# MC33797.net
KiCad netlist of a schematic drawn in Altium Designer
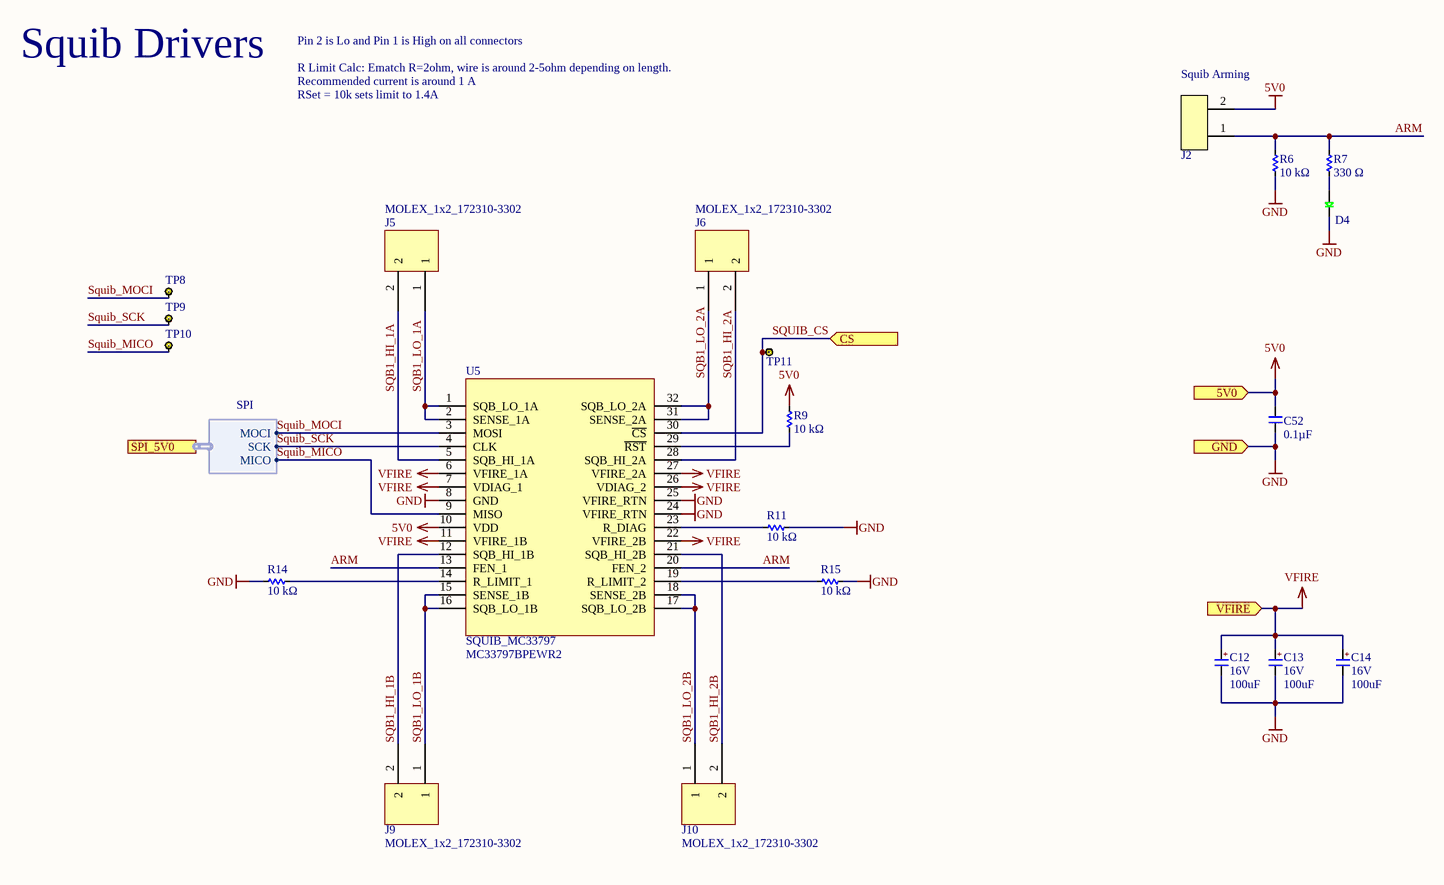
[diagram p0: MC33797.SchDoc]

(export (version "E")
  (design (tool "Eeschema 10.0.6"))
  (components
    (comp (ref "C12")
      (value "TPSC107M016R0200")
      (footprint "CAPCP6032X28N")
      (description "Cap Tant Solid 100uF 16V C CASE 20% (6 X 3.2 X 2.6mm) SMD 6032-28 0.2 Ohm 125°C T/R")
      (fields
        (field (name "CAPACITANCE") "100uF")
        (field (name "VOLTAGE RATING") "16V")
        (field (name "TOLERANCE") "20%")
      )
      (libsource (lib "Stanford Student Space Initiative") (part "CAP_TANT"))
    )
    (comp (ref "C13")
      (value "TPSC107M016R0200")
      (footprint "CAPCP6032X28N")
      (description "Cap Tant Solid 100uF 16V C CASE 20% (6 X 3.2 X 2.6mm) SMD 6032-28 0.2 Ohm 125°C T/R")
      (fields
        (field (name "CAPACITANCE") "100uF")
        (field (name "VOLTAGE RATING") "16V")
        (field (name "TOLERANCE") "20%")
      )
      (libsource (lib "Stanford Student Space Initiative") (part "CAP_TANT"))
    )
    (comp (ref "C14")
      (value "TPSC107M016R0200")
      (footprint "CAPCP6032X28N")
      (description "Cap Tant Solid 100uF 16V C CASE 20% (6 X 3.2 X 2.6mm) SMD 6032-28 0.2 Ohm 125°C T/R")
      (fields
        (field (name "CAPACITANCE") "100uF")
        (field (name "VOLTAGE RATING") "16V")
        (field (name "TOLERANCE") "20%")
      )
      (libsource (lib "Stanford Student Space Initiative") (part "CAP_TANT"))
    )
    (comp (ref "C52")
      (value "490-1519-1-ND")
      (footprint "C0603")
      (description "CAP CER 0603 0.1µF X7R 50V 10%")
      (fields
        (field (name "CAPACITANCE (SHORTHAND)") "0.1µF")
        (field (name "MANUFACTURER") "Murata Electronics North America")
      )
      (libsource (lib "Stanford Student Space Initiative") (part "__template_cap"))
    )
    (comp (ref "D4")
      (value "LED_C503B-GCS-CB0C0781")
      (footprint "LED_TH_5MM")
      (description "LED GREEN CLEAR 5MM ROUND T/H")
      (fields
        (field (name "MANUFACTURER") "Cree")
        (field (name "MANUFACTURER PART NUMBER") "C503B-GCS-CB0C0781")
      )
      (libsource (lib "Stanford Student Space Initiative") (part "LED_C503B-GCS-CB0C0781"))
    )
    (comp (ref "J2")
      (value "CONN_1x2")
      (footprint "CONN_1x2_100MIL")
      (description "CONN HEADER 2POS VERT T/H")
      (fields (field (name "MANUFACTURER PART NUMBER") "77311-118-02LF") (field (name "MANUFACTURER") "FCI"))
      (libsource (lib "Stanford Student Space Initiative") (part "Symbol"))
    )
    (comp (ref "J5")
      (value "MOLEX_1x2_172310-3302")
      (footprint "Molex 172310-xx02")
      (description "ULTRAFIT CONN HEADER R/A 2POS 3.5MM")
      (libsource (lib "") (part "MOLEX_1x2_1723101102_3"))
    )
    (comp (ref "J6")
      (value "MOLEX_1x2_172310-3302")
      (footprint "Molex 172310-xx02")
      (description "ULTRAFIT CONN HEADER R/A 2POS 3.5MM")
      (libsource (lib "Stanford Student Space Initiative") (part "MOLEX_1x2_1723101102"))
    )
    (comp (ref "J9")
      (value "MOLEX_1x2_172310-3302")
      (footprint "Molex 172310-xx02")
      (description "ULTRAFIT CONN HEADER R/A 2POS 3.5MM")
      (libsource (lib "") (part "MOLEX_1x2_1723101102_2"))
    )
    (comp (ref "J10")
      (value "MOLEX_1x2_172310-3302")
      (footprint "Molex 172310-xx02")
      (description "ULTRAFIT CONN HEADER R/A 2POS 3.5MM")
      (libsource (lib "") (part "MOLEX_1x2_1723101102_1"))
    )
    (comp (ref "R6")
      (value "311-10.0KHRCT-ND")
      (footprint "R0603")
      (description "RES SMD 10K OHM 1% 1/10W 0603")
      (fields
        (field (name "RESISTANCE") "10 kΩ")
        (field (name "MANUFACTURER PART NUMBER") "RC0603FR-0710KL")
        (field (name "MANUFACTURER") "Yageo")
      )
      (libsource (lib "Stanford Student Space Initiative") (part "__template_resistor"))
    )
    (comp (ref "R7")
      (value "311-330HRCT-ND")
      (footprint "R0603")
      (description "RES SMD 330 OHM 1% 1/10W 0603")
      (fields
        (field (name "RESISTANCE") "330 Ω")
        (field (name "MANUFACTURER PART NUMBER") "RC0603FR-07330RL")
        (field (name "MANUFACTURER") "Yageo")
      )
      (libsource (lib "Stanford Student Space Initiative") (part "__template_resistor"))
    )
    (comp (ref "R9")
      (value "311-10.0KHRCT-ND")
      (footprint "R0603")
      (description "RES SMD 10K OHM 1% 1/10W 0603")
      (fields
        (field (name "RESISTANCE") "10 kΩ")
        (field (name "MANUFACTURER PART NUMBER") "RC0603FR-0710KL")
        (field (name "MANUFACTURER") "Yageo")
      )
      (libsource (lib "Stanford Student Space Initiative") (part "__template_resistor"))
    )
    (comp (ref "R11")
      (value "311-10.0KHRCT-ND")
      (footprint "R0603")
      (description "RES SMD 10K OHM 1% 1/10W 0603")
      (fields
        (field (name "RESISTANCE") "10 kΩ")
        (field (name "MANUFACTURER PART NUMBER") "RC0603FR-0710KL")
        (field (name "MANUFACTURER") "Yageo")
      )
      (libsource (lib "Stanford Student Space Initiative") (part "__template_resistor"))
    )
    (comp (ref "R14")
      (value "311-10.0KHRCT-ND")
      (footprint "R0603")
      (description "RES SMD 10K OHM 1% 1/10W 0603")
      (fields
        (field (name "RESISTANCE") "10 kΩ")
        (field (name "MANUFACTURER PART NUMBER") "RC0603FR-0710KL")
        (field (name "MANUFACTURER") "Yageo")
      )
      (libsource (lib "Stanford Student Space Initiative") (part "__template_resistor"))
    )
    (comp (ref "R15")
      (value "311-10.0KHRCT-ND")
      (footprint "R0603")
      (description "RES SMD 10K OHM 1% 1/10W 0603")
      (fields
        (field (name "RESISTANCE") "10 kΩ")
        (field (name "MANUFACTURER PART NUMBER") "RC0603FR-0710KL")
        (field (name "MANUFACTURER") "Yageo")
      )
      (libsource (lib "Stanford Student Space Initiative") (part "__template_resistor"))
    )
    (comp (ref "TP8")
      (value "TEST_POINT_BLACK_KEYSTONE_5001")
      (footprint "TEST_POINT_BLACK_KEYSTONE_5001-Footprint-1")
      (description "BLACK T/H TEST POINT")
      (fields
        (field (name "MANUFACTURER PART NUMBER") "5001")
        (field (name "MANUFACTURER") "Keystone Electronics")
      )
      (libsource (lib "Stanford Student Space Initiative") (part "TEST_POINT_BLACK_KEYSTONE_5001"))
    )
    (comp (ref "TP9")
      (value "TEST_POINT_BLACK_KEYSTONE_5001")
      (footprint "TEST_POINT_BLACK_KEYSTONE_5001-Footprint-1")
      (description "BLACK T/H TEST POINT")
      (fields
        (field (name "MANUFACTURER PART NUMBER") "5001")
        (field (name "MANUFACTURER") "Keystone Electronics")
      )
      (libsource (lib "Stanford Student Space Initiative") (part "TEST_POINT_BLACK_KEYSTONE_5001"))
    )
    (comp (ref "TP10")
      (value "TEST_POINT_BLACK_KEYSTONE_5001")
      (footprint "TEST_POINT_BLACK_KEYSTONE_5001-Footprint-1")
      (description "BLACK T/H TEST POINT")
      (fields
        (field (name "MANUFACTURER PART NUMBER") "5001")
        (field (name "MANUFACTURER") "Keystone Electronics")
      )
      (libsource (lib "Stanford Student Space Initiative") (part "TEST_POINT_BLACK_KEYSTONE_5001"))
    )
    (comp (ref "TP11")
      (value "TEST_POINT_BLACK_KEYSTONE_5001")
      (footprint "TEST_POINT_BLACK_KEYSTONE_5001-Footprint-1")
      (description "BLACK T/H TEST POINT")
      (fields
        (field (name "MANUFACTURER PART NUMBER") "5001")
        (field (name "MANUFACTURER") "Keystone Electronics")
      )
      (libsource (lib "Stanford Student Space Initiative") (part "TEST_POINT_BLACK_KEYSTONE_5001"))
    )
    (comp (ref "U5")
      (value "SQUIB_MC33797")
      (footprint "SOT1762-1")
      (fields
        (field (name "MANUFACTURER") "NXP USA Inc.")
        (field (name "MANUFACTURER PART NUMBER") "MC33797BPEWR2")
      )
      (libsource (lib "Stanford Student Space Initiative") (part "SQUIB_MC33797"))
    )
  )
  (nets
    (net (code "2") (name "/ARM") (class "Default")
      (node (ref "J2") (pin "1") (pinfunction "1_1") (pintype "passive"))
      (node (ref "R6") (pin "1") (pinfunction "1_1") (pintype "passive"))
      (node (ref "R7") (pin "2") (pinfunction "2_2") (pintype "passive"))
      (node (ref "U5") (pin "13") (pinfunction "FEN_1_13") (pintype "passive"))
      (node (ref "U5") (pin "20") (pinfunction "FEN_2_20") (pintype "passive"))
    )
    (net (code "3") (name "/SQB1_HI_1A") (class "Default")
      (node (ref "J5") (pin "2") (pinfunction "2_2") (pintype "passive"))
      (node (ref "U5") (pin "5") (pinfunction "SQB_HI_1A_5") (pintype "passive"))
    )
    (net (code "4") (name "/SQB1_HI_1B") (class "Default")
      (node (ref "J9") (pin "2") (pinfunction "2_2") (pintype "passive"))
      (node (ref "U5") (pin "12") (pinfunction "SQB_HI_1B_12") (pintype "passive"))
    )
    (net (code "5") (name "/SQB1_HI_2A") (class "Default")
      (node (ref "J6") (pin "2") (pinfunction "2_2") (pintype "passive"))
      (node (ref "U5") (pin "28") (pinfunction "SQB_HI_2A_28") (pintype "passive"))
    )
    (net (code "6") (name "/SQB1_HI_2B") (class "Default")
      (node (ref "J10") (pin "2") (pinfunction "2_2") (pintype "passive"))
      (node (ref "U5") (pin "21") (pinfunction "SQB_HI_2B_21") (pintype "passive"))
    )
    (net (code "7") (name "/SQB1_LO_1A") (class "Default")
      (node (ref "J5") (pin "1") (pinfunction "1_1") (pintype "passive"))
      (node (ref "U5") (pin "1") (pinfunction "SQB_LO_1A_1") (pintype "passive"))
      (node (ref "U5") (pin "2") (pinfunction "SENSE_1A_2") (pintype "passive"))
    )
    (net (code "8") (name "/SQB1_LO_1B") (class "Default")
      (node (ref "J9") (pin "1") (pinfunction "1_1") (pintype "passive"))
      (node (ref "U5") (pin "15") (pinfunction "SENSE_1B_15") (pintype "passive"))
      (node (ref "U5") (pin "16") (pinfunction "SQB_LO_1B_16") (pintype "passive"))
    )
    (net (code "9") (name "/SQB1_LO_2A") (class "Default")
      (node (ref "J6") (pin "1") (pinfunction "1_1") (pintype "passive"))
      (node (ref "U5") (pin "31") (pinfunction "SENSE_2A_31") (pintype "passive"))
      (node (ref "U5") (pin "32") (pinfunction "SQB_LO_2A_32") (pintype "passive"))
    )
    (net (code "10") (name "/SQB1_LO_2B") (class "Default")
      (node (ref "J10") (pin "1") (pinfunction "1_1") (pintype "passive"))
      (node (ref "U5") (pin "17") (pinfunction "SQB_LO_2B_17") (pintype "passive"))
      (node (ref "U5") (pin "18") (pinfunction "SENSE_2B_18") (pintype "passive"))
    )
    (net (code "11") (name "/SQUIB_CS") (class "Default")
      (node (ref "TP11") (pin "1") (pinfunction "1_1") (pintype "passive"))
      (node (ref "U5") (pin "30") (pinfunction "~{CS}_30") (pintype "passive"))
    )
    (net (code "12") (name "/Squib_MICO") (class "Default")
      (node (ref "TP10") (pin "1") (pinfunction "1_1") (pintype "passive"))
      (node (ref "U5") (pin "9") (pinfunction "MISO_9") (pintype "passive"))
    )
    (net (code "13") (name "/Squib_MOCI") (class "Default")
      (node (ref "TP8") (pin "1") (pinfunction "1_1") (pintype "passive"))
      (node (ref "U5") (pin "3") (pinfunction "MOSI_3") (pintype "passive"))
    )
    (net (code "14") (name "/Squib_SCK") (class "Default")
      (node (ref "TP9") (pin "1") (pinfunction "1_1") (pintype "passive"))
      (node (ref "U5") (pin "4") (pinfunction "CLK_4") (pintype "passive"))
    )
    (net (code "16") (name "5V0") (class "Default")
      (node (ref "C52") (pin "1") (pintype "passive"))
      (node (ref "J2") (pin "2") (pinfunction "2_2") (pintype "passive"))
      (node (ref "R9") (pin "2") (pinfunction "2_2") (pintype "passive"))
      (node (ref "U5") (pin "10") (pinfunction "VDD_10") (pintype "passive"))
    )
    (net (code "17") (name "GND") (class "Default")
      (node (ref "C12") (pin "2") (pinfunction "K_2") (pintype "passive"))
      (node (ref "C13") (pin "2") (pinfunction "K_2") (pintype "passive"))
      (node (ref "C14") (pin "2") (pinfunction "K_2") (pintype "passive"))
      (node (ref "C52") (pin "2") (pintype "passive"))
      (node (ref "D4") (pin "2") (pinfunction "K_2") (pintype "passive"))
      (node (ref "R11") (pin "2") (pinfunction "2_2") (pintype "passive"))
      (node (ref "R14") (pin "1") (pinfunction "1_1") (pintype "passive"))
      (node (ref "R15") (pin "2") (pinfunction "2_2") (pintype "passive"))
      (node (ref "R6") (pin "2") (pinfunction "2_2") (pintype "passive"))
      (node (ref "U5") (pin "24") (pinfunction "VFIRE_RTN_24") (pintype "passive"))
      (node (ref "U5") (pin "25") (pinfunction "VFIRE_RTN_25") (pintype "passive"))
      (node (ref "U5") (pin "8") (pinfunction "GND_8") (pintype "passive"))
    )
    (net (code "18") (name "Net-(D4-A)") (class "Default")
      (node (ref "D4") (pin "1") (pinfunction "A_1") (pintype "passive"))
      (node (ref "R7") (pin "1") (pinfunction "1_1") (pintype "passive"))
    )
    (net (code "19") (name "Net-(U5-R_DIAG)") (class "Default")
      (node (ref "R11") (pin "1") (pinfunction "1_1") (pintype "passive"))
      (node (ref "U5") (pin "23") (pinfunction "R_DIAG_23") (pintype "passive"))
    )
    (net (code "20") (name "Net-(U5-R_LIMIT_1)") (class "Default")
      (node (ref "R14") (pin "2") (pinfunction "2_2") (pintype "passive"))
      (node (ref "U5") (pin "14") (pinfunction "R_LIMIT_1_14") (pintype "passive"))
    )
    (net (code "21") (name "Net-(U5-R_LIMIT_2)") (class "Default")
      (node (ref "R15") (pin "1") (pinfunction "1_1") (pintype "passive"))
      (node (ref "U5") (pin "19") (pinfunction "R_LIMIT_2_19") (pintype "passive"))
    )
    (net (code "22") (name "Net-(U5-~{RST})") (class "Default")
      (node (ref "R9") (pin "1") (pinfunction "1_1") (pintype "passive"))
      (node (ref "U5") (pin "29") (pinfunction "~{RST}_29") (pintype "passive"))
    )
    (net (code "23") (name "VFIRE") (class "Default")
      (node (ref "C12") (pin "1") (pinfunction "A_1") (pintype "passive"))
      (node (ref "C13") (pin "1") (pinfunction "A_1") (pintype "passive"))
      (node (ref "C14") (pin "1") (pinfunction "A_1") (pintype "passive"))
      (node (ref "U5") (pin "11") (pinfunction "VFIRE_1B_11") (pintype "passive"))
      (node (ref "U5") (pin "22") (pinfunction "VFIRE_2B_22") (pintype "passive"))
      (node (ref "U5") (pin "26") (pinfunction "VDIAG_2_26") (pintype "passive"))
      (node (ref "U5") (pin "27") (pinfunction "VFIRE_2A_27") (pintype "passive"))
      (node (ref "U5") (pin "6") (pinfunction "VFIRE_1A_6") (pintype "passive"))
      (node (ref "U5") (pin "7") (pinfunction "VDIAG_1_7") (pintype "passive"))
    )
  )
)
